# Base.net
KiCad netlist of a schematic drawn in EAGLE
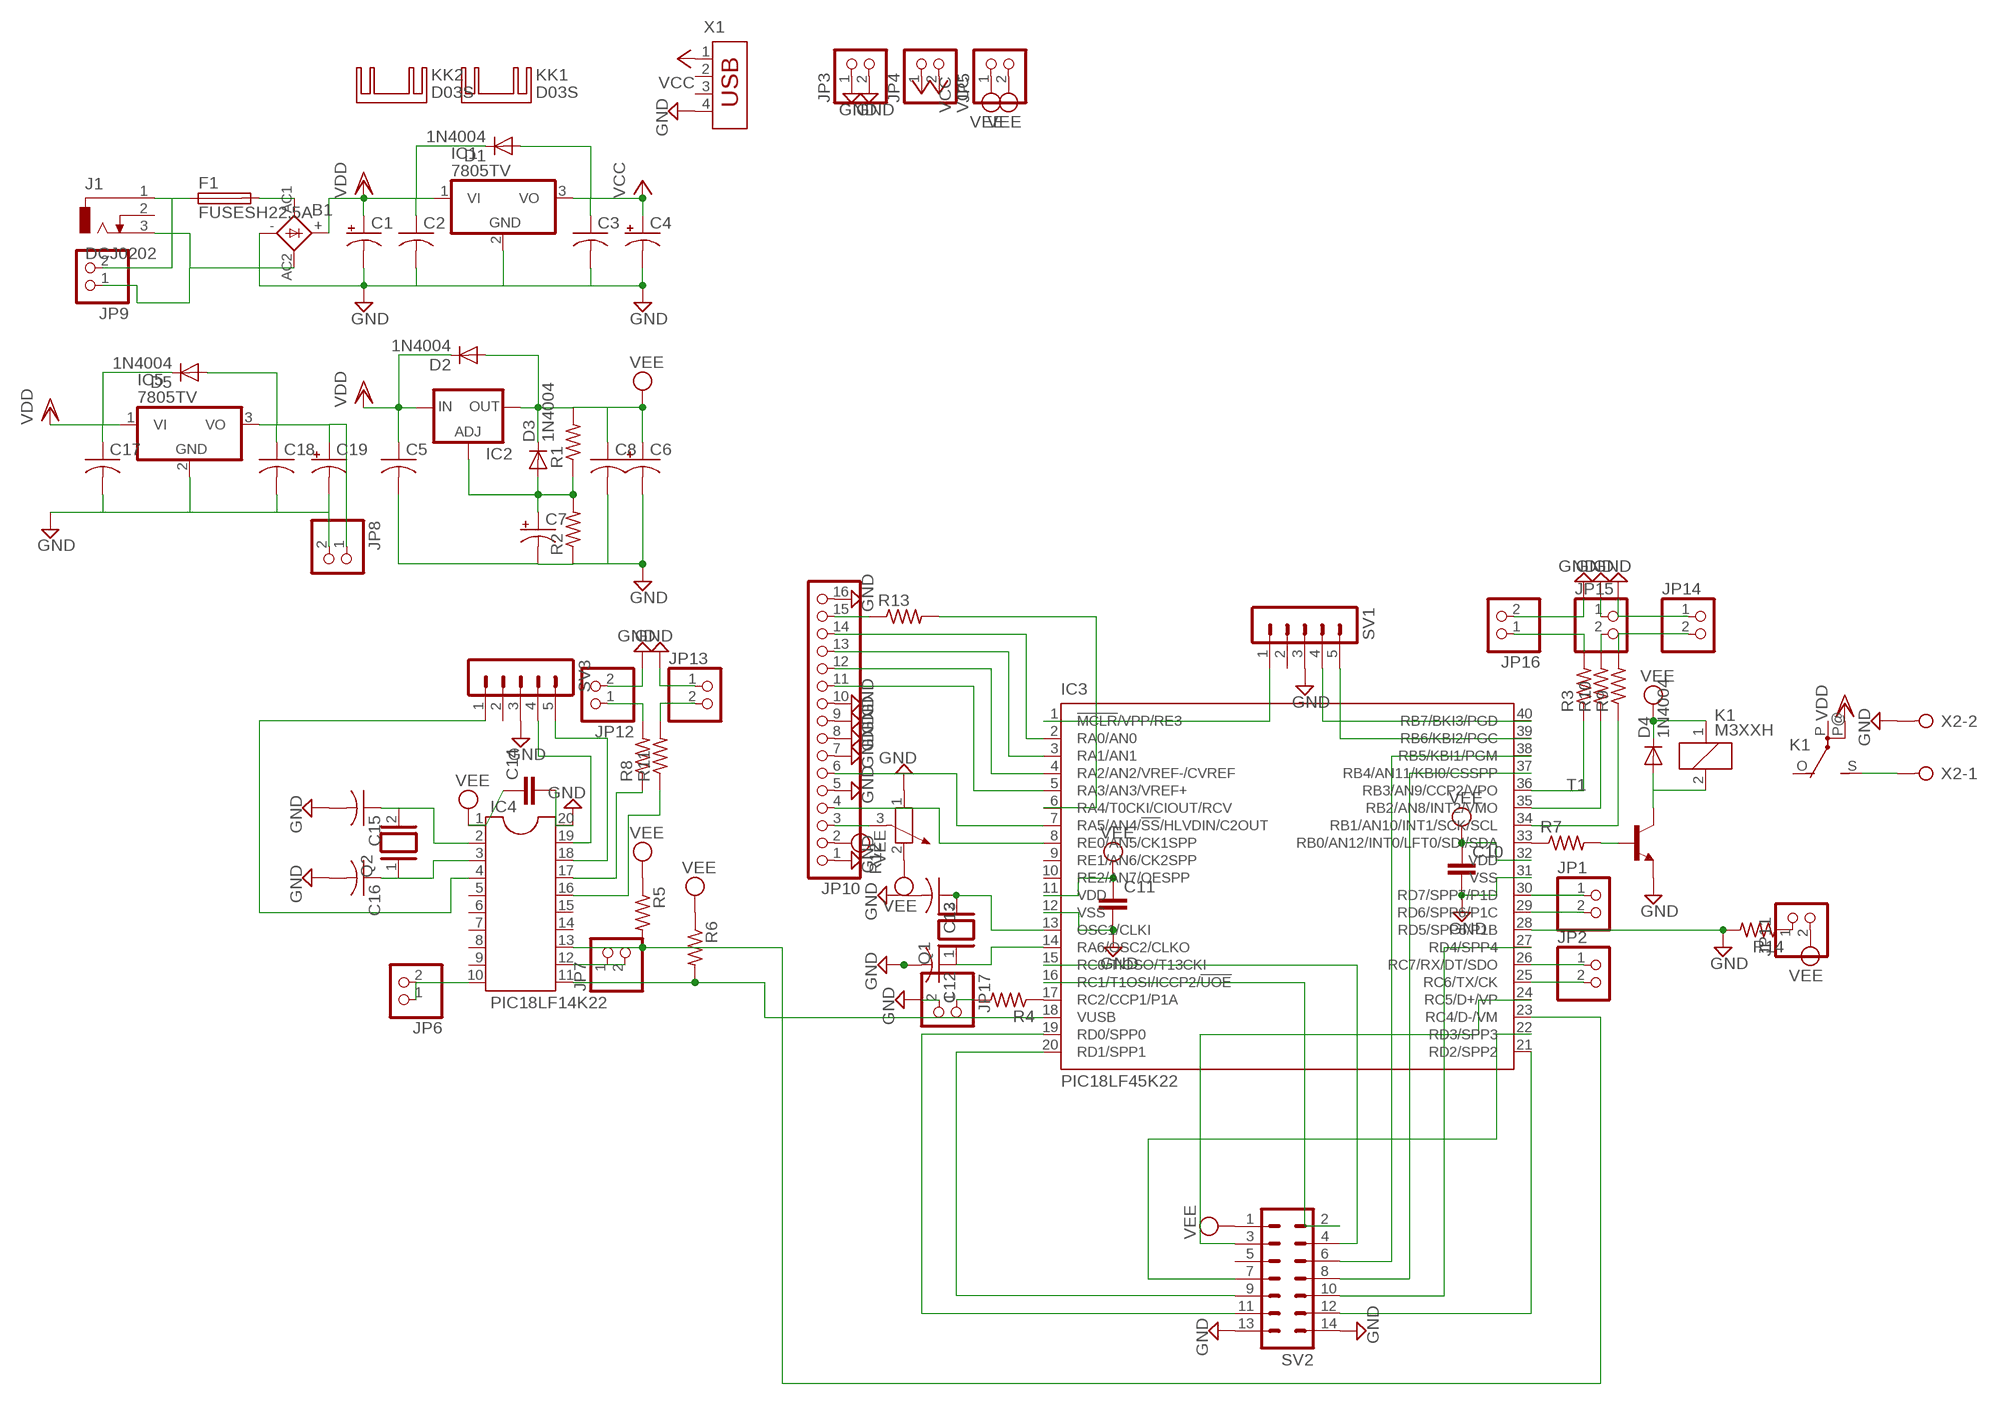
[diagram p0: schematic, sheet 1]

(export (version "E")
  (design (tool "Eeschema 10.0.6"))
  (components
    (comp (ref "B1")
      (value "1KAB")
      (footprint "eagle-import:1KAB")
      (libsource (lib "eagle-import") (part "1KAB"))
    )
    (comp (ref "C1")
      (value "CPOL-USE5-13")
      (footprint "eagle-import:E5-13")
      (libsource (lib "eagle-import") (part "CPOL-USE5-13"))
    )
    (comp (ref "C2")
      (value "C-US050-030X075")
      (footprint "eagle-import:C050-030X075")
      (libsource (lib "eagle-import") (part "C-US050-030X075"))
    )
    (comp (ref "C3")
      (value "C-US050-030X075")
      (footprint "eagle-import:C050-030X075")
      (libsource (lib "eagle-import") (part "C-US050-030X075"))
    )
    (comp (ref "C4")
      (value "CPOL-USE5-13")
      (footprint "eagle-import:E5-13")
      (libsource (lib "eagle-import") (part "CPOL-USE5-13"))
    )
    (comp (ref "C5")
      (value "C-US050-030X075")
      (footprint "eagle-import:C050-030X075")
      (libsource (lib "eagle-import") (part "C-US050-030X075"))
    )
    (comp (ref "C6")
      (value "CPOL-USE2.5-7")
      (footprint "eagle-import:E2,5-7")
      (libsource (lib "eagle-import") (part "CPOL-USE2.5-7"))
    )
    (comp (ref "C7")
      (value "CPOL-USE2.5-5")
      (footprint "eagle-import:E2,5-5")
      (libsource (lib "eagle-import") (part "CPOL-USE2.5-5"))
    )
    (comp (ref "C8")
      (value "C-US050-030X075")
      (footprint "eagle-import:C050-030X075")
      (libsource (lib "eagle-import") (part "C-US050-030X075"))
    )
    (comp (ref "C10")
      (value "C-EU025-030X050")
      (footprint "eagle-import:C025-030X050")
      (libsource (lib "eagle-import") (part "C-EU025-030X050"))
    )
    (comp (ref "C11")
      (value "C-EU025-030X050")
      (footprint "eagle-import:C025-030X050")
      (libsource (lib "eagle-import") (part "C-EU025-030X050"))
    )
    (comp (ref "C12")
      (value "C-US025-030X050")
      (footprint "eagle-import:C025-030X050")
      (libsource (lib "eagle-import") (part "C-US025-030X050"))
    )
    (comp (ref "C13")
      (value "C-US025-030X050")
      (footprint "eagle-import:C025-030X050")
      (libsource (lib "eagle-import") (part "C-US025-030X050"))
    )
    (comp (ref "C14")
      (value "C-EU025-030X050")
      (footprint "eagle-import:C025-030X050")
      (libsource (lib "eagle-import") (part "C-EU025-030X050"))
    )
    (comp (ref "C15")
      (value "C-US025-030X050")
      (footprint "eagle-import:C025-030X050")
      (libsource (lib "eagle-import") (part "C-US025-030X050"))
    )
    (comp (ref "C16")
      (value "C-US025-030X050")
      (footprint "eagle-import:C025-030X050")
      (libsource (lib "eagle-import") (part "C-US025-030X050"))
    )
    (comp (ref "C17")
      (value "C-US050-030X075")
      (footprint "eagle-import:C050-030X075")
      (libsource (lib "eagle-import") (part "C-US050-030X075"))
    )
    (comp (ref "C18")
      (value "C-US050-030X075")
      (footprint "eagle-import:C050-030X075")
      (libsource (lib "eagle-import") (part "C-US050-030X075"))
    )
    (comp (ref "C19")
      (value "CPOL-USE5-10.5")
      (footprint "eagle-import:E5-10,5")
      (libsource (lib "eagle-import") (part "CPOL-USE5-10.5"))
    )
    (comp (ref "D1")
      (value "1N4004")
      (footprint "eagle-import:DO41-10")
      (libsource (lib "eagle-import") (part "1N4004"))
    )
    (comp (ref "D2")
      (value "1N4004")
      (footprint "eagle-import:DO41-10")
      (libsource (lib "eagle-import") (part "1N4004"))
    )
    (comp (ref "D3")
      (value "1N4004")
      (footprint "eagle-import:DO41-10")
      (libsource (lib "eagle-import") (part "1N4004"))
    )
    (comp (ref "D4")
      (value "1N4004")
      (footprint "eagle-import:DO41-10")
      (libsource (lib "eagle-import") (part "1N4004"))
    )
    (comp (ref "D5")
      (value "1N4004")
      (footprint "eagle-import:DO41-10")
      (libsource (lib "eagle-import") (part "1N4004"))
    )
    (comp (ref "F1")
      (value "FUSESH22,5A")
      (footprint "eagle-import:SH22,5A")
      (libsource (lib "eagle-import") (part "FUSESH22,5A"))
    )
    (comp (ref "IC1")
      (value "7805TV")
      (footprint "eagle-import:TO220V")
      (libsource (lib "eagle-import") (part "78TV05"))
    )
    (comp (ref "IC2")
      (value "LM317TS")
      (footprint "eagle-import:317TS")
      (libsource (lib "eagle-import") (part "LM317TS"))
    )
    (comp (ref "IC3")
      (value "PIC18LF45K22")
      (footprint "eagle-import:DIL40")
      (fields (field (name "MF") "MICROCHIP") (field (name "MPN") "PIC18F4550-I/P"))
      (libsource (lib "eagle-import") (part "PIC18F4_40550"))
    )
    (comp (ref "IC4")
      (value "PIC18LF14K22")
      (footprint "eagle-import:DIL20")
      (libsource (lib "eagle-import") (part "DIL20"))
    )
    (comp (ref "IC5")
      (value "7805TV")
      (footprint "eagle-import:TO220V")
      (libsource (lib "eagle-import") (part "78TV05"))
    )
    (comp (ref "J1")
      (value "DCJ0202")
      (footprint "eagle-import:DCJ0202")
      (libsource (lib "eagle-import") (part "DCJ0202"))
    )
    (comp (ref "JP1")
      (value "PINHD-1X2")
      (footprint "eagle-import:1X02")
      (libsource (lib "eagle-import") (part "PINHD-1X2"))
    )
    (comp (ref "JP2")
      (value "PINHD-1X2")
      (footprint "eagle-import:1X02")
      (libsource (lib "eagle-import") (part "PINHD-1X2"))
    )
    (comp (ref "JP3")
      (value "PINHD-1X2")
      (footprint "eagle-import:1X02")
      (libsource (lib "eagle-import") (part "PINHD-1X2"))
    )
    (comp (ref "JP4")
      (value "PINHD-1X2")
      (footprint "eagle-import:1X02")
      (libsource (lib "eagle-import") (part "PINHD-1X2"))
    )
    (comp (ref "JP5")
      (value "PINHD-1X2")
      (footprint "eagle-import:1X02")
      (libsource (lib "eagle-import") (part "PINHD-1X2"))
    )
    (comp (ref "JP6")
      (value "PINHD-1X2")
      (footprint "eagle-import:1X02")
      (libsource (lib "eagle-import") (part "PINHD-1X2"))
    )
    (comp (ref "JP7")
      (value "PINHD-1X2")
      (footprint "eagle-import:1X02")
      (libsource (lib "eagle-import") (part "PINHD-1X2"))
    )
    (comp (ref "JP8")
      (value "PINHD-1X2")
      (footprint "eagle-import:1X02")
      (libsource (lib "eagle-import") (part "PINHD-1X2"))
    )
    (comp (ref "JP9")
      (value "PINHD-1X2")
      (footprint "eagle-import:1X02")
      (libsource (lib "eagle-import") (part "PINHD-1X2"))
    )
    (comp (ref "JP10")
      (value "PINHD-1X16")
      (footprint "eagle-import:1X16")
      (libsource (lib "eagle-import") (part "PINHD-1X16"))
    )
    (comp (ref "JP11")
      (value "PINHD-1X2")
      (footprint "eagle-import:1X02")
      (libsource (lib "eagle-import") (part "PINHD-1X2"))
    )
    (comp (ref "JP12")
      (value "PINHD-1X2")
      (footprint "eagle-import:1X02")
      (libsource (lib "eagle-import") (part "PINHD-1X2"))
    )
    (comp (ref "JP13")
      (value "PINHD-1X2")
      (footprint "eagle-import:1X02")
      (libsource (lib "eagle-import") (part "PINHD-1X2"))
    )
    (comp (ref "JP14")
      (value "PINHD-1X2")
      (footprint "eagle-import:1X02")
      (libsource (lib "eagle-import") (part "PINHD-1X2"))
    )
    (comp (ref "JP15")
      (value "PINHD-1X2")
      (footprint "eagle-import:1X02")
      (libsource (lib "eagle-import") (part "PINHD-1X2"))
    )
    (comp (ref "JP16")
      (value "PINHD-1X2")
      (footprint "eagle-import:1X02")
      (libsource (lib "eagle-import") (part "PINHD-1X2"))
    )
    (comp (ref "JP17")
      (value "PINHD-1X2")
      (footprint "eagle-import:1X02")
      (libsource (lib "eagle-import") (part "PINHD-1X2"))
    )
    (comp (ref "K1")
      (value "M3XXH")
      (footprint "eagle-import:M3XXH")
      (libsource (lib "eagle-import") (part "M3XXH"))
    )
    (comp (ref "KK1")
      (value "D03S")
      (footprint "eagle-import:D03S")
      (libsource (lib "eagle-import") (part "D03S"))
    )
    (comp (ref "KK2")
      (value "D03S")
      (footprint "eagle-import:D03S")
      (libsource (lib "eagle-import") (part "D03S"))
    )
    (comp (ref "Q1")
      (value "XTAL/S")
      (footprint "eagle-import:QS")
      (libsource (lib "eagle-import") (part "XTAL/S"))
    )
    (comp (ref "Q2")
      (value "XTAL/S")
      (footprint "eagle-import:QS")
      (libsource (lib "eagle-import") (part "XTAL/S"))
    )
    (comp (ref "R1")
      (value "R-US_0207/10")
      (footprint "eagle-import:0207_10")
      (libsource (lib "eagle-import") (part "R-US_0207/10"))
    )
    (comp (ref "R2")
      (value "R-US_0207/10")
      (footprint "eagle-import:0207_10")
      (libsource (lib "eagle-import") (part "R-US_0207/10"))
    )
    (comp (ref "R3")
      (value "R-US_0207/10")
      (footprint "eagle-import:0207_10")
      (libsource (lib "eagle-import") (part "R-US_0207/10"))
    )
    (comp (ref "R4")
      (value "R-US_0207/10")
      (footprint "eagle-import:0207_10")
      (libsource (lib "eagle-import") (part "R-US_0207/10"))
    )
    (comp (ref "R5")
      (value "R-US_0207/10")
      (footprint "eagle-import:0207_10")
      (libsource (lib "eagle-import") (part "R-US_0207/10"))
    )
    (comp (ref "R6")
      (value "R-US_0207/10")
      (footprint "eagle-import:0207_10")
      (libsource (lib "eagle-import") (part "R-US_0207/10"))
    )
    (comp (ref "R7")
      (value "R-US_0207/10")
      (footprint "eagle-import:0207_10")
      (libsource (lib "eagle-import") (part "R-US_0207/10"))
    )
    (comp (ref "R8")
      (value "R-US_0207/10")
      (footprint "eagle-import:0207_10")
      (libsource (lib "eagle-import") (part "R-US_0207/10"))
    )
    (comp (ref "R9")
      (value "R-US_0207/10")
      (footprint "eagle-import:0207_10")
      (libsource (lib "eagle-import") (part "R-US_0207/10"))
    )
    (comp (ref "R10")
      (value "R-US_0207/10")
      (footprint "eagle-import:0207_10")
      (libsource (lib "eagle-import") (part "R-US_0207/10"))
    )
    (comp (ref "R11")
      (value "R-US_0207/10")
      (footprint "eagle-import:0207_10")
      (libsource (lib "eagle-import") (part "R-US_0207/10"))
    )
    (comp (ref "R12")
      (value "POTENTIOMETER_PT-10")
      (footprint "eagle-import:PT-10")
      (libsource (lib "eagle-import") (part "POTENTIOMETER_PT-10"))
    )
    (comp (ref "R13")
      (value "R-US_0207/10")
      (footprint "eagle-import:0207_10")
      (libsource (lib "eagle-import") (part "R-US_0207/10"))
    )
    (comp (ref "R14")
      (value "R-US_0207/10")
      (footprint "eagle-import:0207_10")
      (libsource (lib "eagle-import") (part "R-US_0207/10"))
    )
    (comp (ref "SV1")
      (value "MA05-1")
      (footprint "eagle-import:MA05-1")
      (libsource (lib "eagle-import") (part "MA05-1"))
    )
    (comp (ref "SV2")
      (value "MA07-2")
      (footprint "eagle-import:MA07-2")
      (libsource (lib "eagle-import") (part "MA07-2"))
    )
    (comp (ref "SV3")
      (value "MA05-1")
      (footprint "eagle-import:MA05-1")
      (fields (field (name "OC_FARNELL") "unknown") (field (name "OC_NEWARK") "unknown"))
      (libsource (lib "eagle-import") (part "MA05-1"))
    )
    (comp (ref "T1")
      (value "BC547-NPN-TO92-CBE")
      (footprint "eagle-import:TO92-CBE")
      (libsource (lib "eagle-import") (part "-NPN-TO92-CBEBC547"))
    )
    (comp (ref "X1")
      (value "USB-787616")
      (footprint "eagle-import:USB")
      (libsource (lib "eagle-import") (part "USB-787616"))
    )
    (comp (ref "X2")
      (value "W237-02P")
      (footprint "eagle-import:W237-132")
      (libsource (lib "eagle-import") (part "W237-02P"))
    )
  )
  (nets
    (net (code "1") (name "GND") (class "Default")
      (node (ref "B1") (pin "-") (pinfunction "-_-") (pintype "passive"))
      (node (ref "C1") (pin "-") (pinfunction "-_-") (pintype "passive"))
      (node (ref "C10") (pin "2") (pinfunction "2_2") (pintype "passive"))
      (node (ref "C11") (pin "2") (pinfunction "2_2") (pintype "passive"))
      (node (ref "C12") (pin "2") (pinfunction "2_2") (pintype "passive"))
      (node (ref "C13") (pin "2") (pinfunction "2_2") (pintype "passive"))
      (node (ref "C14") (pin "2") (pinfunction "2_2") (pintype "passive"))
      (node (ref "C15") (pin "2") (pinfunction "2_2") (pintype "passive"))
      (node (ref "C16") (pin "2") (pinfunction "2_2") (pintype "passive"))
      (node (ref "C17") (pin "2") (pinfunction "2_2") (pintype "passive"))
      (node (ref "C18") (pin "2") (pinfunction "2_2") (pintype "passive"))
      (node (ref "C19") (pin "-") (pinfunction "-_-") (pintype "passive"))
      (node (ref "C2") (pin "2") (pinfunction "2_2") (pintype "passive"))
      (node (ref "C3") (pin "2") (pinfunction "2_2") (pintype "passive"))
      (node (ref "C4") (pin "-") (pinfunction "-_-") (pintype "passive"))
      (node (ref "C5") (pin "2") (pinfunction "2_2") (pintype "passive"))
      (node (ref "C6") (pin "-") (pinfunction "-_-") (pintype "passive"))
      (node (ref "C7") (pin "-") (pinfunction "-_-") (pintype "passive"))
      (node (ref "C8") (pin "2") (pinfunction "2_2") (pintype "passive"))
      (node (ref "IC1") (pin "2") (pinfunction "GND_2") (pintype "passive"))
      (node (ref "IC3") (pin "12") (pinfunction "VSS_12") (pintype "power_in"))
      (node (ref "IC3") (pin "28") (pinfunction "RD5/SPP5/P1B_28") (pintype "bidirectional"))
      (node (ref "IC3") (pin "31") (pinfunction "VSS_31") (pintype "power_in"))
      (node (ref "IC4") (pin "20") (pinfunction "20_20") (pintype "passive"))
      (node (ref "IC5") (pin "2") (pinfunction "GND_2") (pintype "passive"))
      (node (ref "JP10") (pin "1") (pinfunction "1_1") (pintype "passive"))
      (node (ref "JP10") (pin "10") (pinfunction "10_10") (pintype "passive"))
      (node (ref "JP10") (pin "16") (pinfunction "16_16") (pintype "passive"))
      (node (ref "JP10") (pin "5") (pinfunction "5_5") (pintype "passive"))
      (node (ref "JP10") (pin "7") (pinfunction "7_7") (pintype "passive"))
      (node (ref "JP10") (pin "8") (pinfunction "8_8") (pintype "passive"))
      (node (ref "JP10") (pin "9") (pinfunction "9_9") (pintype "passive"))
      (node (ref "JP12") (pin "2") (pinfunction "2_2") (pintype "passive"))
      (node (ref "JP13") (pin "1") (pinfunction "1_1") (pintype "passive"))
      (node (ref "JP14") (pin "1") (pinfunction "1_1") (pintype "passive"))
      (node (ref "JP15") (pin "1") (pinfunction "1_1") (pintype "passive"))
      (node (ref "JP16") (pin "2") (pinfunction "2_2") (pintype "passive"))
      (node (ref "JP17") (pin "2") (pinfunction "2_2") (pintype "passive"))
      (node (ref "JP3") (pin "1") (pinfunction "1_1") (pintype "passive"))
      (node (ref "JP3") (pin "2") (pinfunction "2_2") (pintype "passive"))
      (node (ref "JP8") (pin "2") (pinfunction "2_2") (pintype "passive"))
      (node (ref "R12") (pin "1") (pinfunction "1_1") (pintype "passive"))
      (node (ref "R14") (pin "2") (pinfunction "2_2") (pintype "passive"))
      (node (ref "R2") (pin "1") (pinfunction "1_1") (pintype "passive"))
      (node (ref "SV1") (pin "3") (pinfunction "3_3") (pintype "passive"))
      (node (ref "SV2") (pin "13") (pinfunction "13_13") (pintype "passive"))
      (node (ref "SV2") (pin "14") (pinfunction "14_14") (pintype "passive"))
      (node (ref "SV3") (pin "3") (pinfunction "3_3") (pintype "passive"))
      (node (ref "T1") (pin "E") (pinfunction "E_E") (pintype "passive"))
      (node (ref "X1") (pin "4") (pinfunction "4_4") (pintype "passive"))
      (node (ref "X2") (pin "2") (pinfunction "KL_2") (pintype "passive"))
    )
    (net (code "2") (name "Net-(B1-PadAC1)") (class "Default")
      (node (ref "B1") (pin "AC1") (pinfunction "AC1_AC1") (pintype "passive"))
      (node (ref "F1") (pin "2") (pinfunction "2_2") (pintype "passive"))
    )
    (net (code "3") (name "Net-(B1-PadAC2)") (class "Default")
      (node (ref "B1") (pin "AC2") (pinfunction "AC2_AC2") (pintype "passive"))
      (node (ref "J1") (pin "3") (pinfunction "3_3") (pintype "passive"))
      (node (ref "JP9") (pin "1") (pinfunction "1_1") (pintype "passive"))
    )
    (net (code "4") (name "Net-(C15-Pad1)") (class "Default")
      (node (ref "C15") (pin "1") (pinfunction "1_1") (pintype "passive"))
      (node (ref "IC4") (pin "2") (pinfunction "2_2") (pintype "passive"))
      (node (ref "Q2") (pin "2") (pinfunction "2_2") (pintype "passive"))
    )
    (net (code "5") (name "Net-(C16-Pad1)") (class "Default")
      (node (ref "C16") (pin "1") (pinfunction "1_1") (pintype "passive"))
      (node (ref "IC4") (pin "3") (pinfunction "3_3") (pintype "passive"))
      (node (ref "Q2") (pin "1") (pinfunction "1_1") (pintype "passive"))
    )
    (net (code "6") (name "Net-(D4-PadA)") (class "Default")
      (node (ref "D4") (pin "A") (pinfunction "A_A") (pintype "passive"))
      (node (ref "K1") (pin "2") (pinfunction "2_2") (pintype "passive"))
      (node (ref "T1") (pin "C") (pinfunction "C_C") (pintype "passive"))
    )
    (net (code "7") (name "Net-(F1-Pad1)") (class "Default")
      (node (ref "F1") (pin "1") (pinfunction "1_1") (pintype "passive"))
      (node (ref "J1") (pin "1") (pinfunction "1_1") (pintype "passive"))
      (node (ref "JP9") (pin "2") (pinfunction "2_2") (pintype "passive"))
    )
    (net (code "8") (name "Net-(IC2-ADJ)") (class "Default")
      (node (ref "C7") (pin "+") (pinfunction "+_+") (pintype "passive"))
      (node (ref "D3") (pin "A") (pinfunction "A_A") (pintype "passive"))
      (node (ref "IC2") (pin "1") (pinfunction "ADJ_1") (pintype "input"))
      (node (ref "R1") (pin "1") (pinfunction "1_1") (pintype "passive"))
      (node (ref "R2") (pin "2") (pinfunction "2_2") (pintype "passive"))
    )
    (net (code "9") (name "Net-(IC3-OSC1{slash}CLKI)") (class "Default")
      (node (ref "C13") (pin "1") (pinfunction "1_1") (pintype "passive"))
      (node (ref "IC3") (pin "13") (pinfunction "OSC1/CLKI_13") (pintype "input"))
      (node (ref "Q1") (pin "2") (pinfunction "2_2") (pintype "passive"))
    )
    (net (code "10") (name "Net-(IC3-RA0{slash}AN0)") (class "Default")
      (node (ref "IC3") (pin "2") (pinfunction "RA0/AN0_2") (pintype "bidirectional"))
      (node (ref "JP10") (pin "14") (pinfunction "14_14") (pintype "passive"))
    )
    (net (code "11") (name "Net-(IC3-RA1{slash}AN1)") (class "Default")
      (node (ref "IC3") (pin "3") (pinfunction "RA1/AN1_3") (pintype "bidirectional"))
      (node (ref "JP10") (pin "13") (pinfunction "13_13") (pintype "passive"))
    )
    (net (code "12") (name "Net-(IC3-RA2{slash}AN2{slash}VREF-{slash}CVREF)") (class "Default")
      (node (ref "IC3") (pin "4") (pinfunction "RA2/AN2/VREF-/CVREF_4") (pintype "bidirectional"))
      (node (ref "JP10") (pin "12") (pinfunction "12_12") (pintype "passive"))
    )
    (net (code "13") (name "Net-(IC3-RA3{slash}AN3{slash}VREF+)") (class "Default")
      (node (ref "IC3") (pin "5") (pinfunction "RA3/AN3/VREF+_5") (pintype "bidirectional"))
      (node (ref "JP10") (pin "11") (pinfunction "11_11") (pintype "passive"))
    )
    (net (code "14") (name "Net-(IC3-RA4{slash}T0CKI{slash}CIOUT{slash}RCV)") (class "Default")
      (node (ref "IC3") (pin "6") (pinfunction "RA4/T0CKI/CIOUT/RCV_6") (pintype "bidirectional"))
      (node (ref "R13") (pin "2") (pinfunction "2_2") (pintype "passive"))
    )
    (net (code "15") (name "Net-(IC3-RA5{slash}AN4{slash}~{SS}{slash}HLVDIN{slash}C2OUT)") (class "Default")
      (node (ref "IC3") (pin "7") (pinfunction "RA5/AN4/~{SS}/HLVDIN/C2OUT_7") (pintype "bidirectional"))
      (node (ref "JP10") (pin "6") (pinfunction "6_6") (pintype "passive"))
    )
    (net (code "16") (name "Net-(IC3-RA6{slash}OSC2{slash}CLKO)") (class "Default")
      (node (ref "C12") (pin "1") (pinfunction "1_1") (pintype "passive"))
      (node (ref "IC3") (pin "14") (pinfunction "RA6/OSC2/CLKO_14") (pintype "output"))
      (node (ref "Q1") (pin "1") (pinfunction "1_1") (pintype "passive"))
    )
    (net (code "17") (name "Net-(IC3-RB0{slash}AN12{slash}INT0{slash}LFT0{slash}SDI{slash}SDA)") (class "Default")
      (node (ref "IC3") (pin "33") (pinfunction "RB0/AN12/INT0/LFT0/SDI/SDA_33") (pintype "bidirectional"))
      (node (ref "R7") (pin "1") (pinfunction "1_1") (pintype "passive"))
    )
    (net (code "18") (name "Net-(IC3-RB1{slash}AN10{slash}INT1{slash}SCK{slash}SCL)") (class "Default")
      (node (ref "IC3") (pin "34") (pinfunction "RB1/AN10/INT1/SCK/SCL_34") (pintype "bidirectional"))
      (node (ref "R9") (pin "1") (pinfunction "1_1") (pintype "passive"))
    )
    (net (code "19") (name "Net-(IC3-RB2{slash}AN8{slash}INT2{slash}VMO)") (class "Default")
      (node (ref "IC3") (pin "35") (pinfunction "RB2/AN8/INT2/VMO_35") (pintype "bidirectional"))
      (node (ref "R10") (pin "1") (pinfunction "1_1") (pintype "passive"))
    )
    (net (code "20") (name "Net-(IC3-RB3{slash}AN9{slash}CCP2{slash}VPO)") (class "Default")
      (node (ref "IC3") (pin "36") (pinfunction "RB3/AN9/CCP2/VPO_36") (pintype "bidirectional"))
      (node (ref "R3") (pin "1") (pinfunction "1_1") (pintype "passive"))
    )
    (net (code "21") (name "Net-(IC3-RB4{slash}AN11{slash}KBI0{slash}CSSPP)") (class "Default")
      (node (ref "IC3") (pin "37") (pinfunction "RB4/AN11/KBI0/CSSPP_37") (pintype "bidirectional"))
      (node (ref "SV2") (pin "8") (pinfunction "8_8") (pintype "passive"))
    )
    (net (code "22") (name "Net-(IC3-RB5{slash}KBI1{slash}PGM)") (class "Default")
      (node (ref "IC3") (pin "38") (pinfunction "RB5/KBI1/PGM_38") (pintype "bidirectional"))
      (node (ref "SV2") (pin "6") (pinfunction "6_6") (pintype "passive"))
    )
    (net (code "23") (name "Net-(IC3-RB6{slash}KBI2{slash}PGC)") (class "Default")
      (node (ref "IC3") (pin "39") (pinfunction "RB6/KBI2/PGC_39") (pintype "bidirectional"))
      (node (ref "SV1") (pin "5") (pinfunction "5_5") (pintype "passive"))
    )
    (net (code "24") (name "Net-(IC3-RB7{slash}BKI3{slash}PGD)") (class "Default")
      (node (ref "IC3") (pin "40") (pinfunction "RB7/BKI3/PGD_40") (pintype "bidirectional"))
      (node (ref "SV1") (pin "4") (pinfunction "4_4") (pintype "passive"))
    )
    (net (code "25") (name "Net-(IC3-RC0{slash}TIOSO{slash}T13CKI)") (class "Default")
      (node (ref "IC3") (pin "15") (pinfunction "RC0/TIOSO/T13CKI_15") (pintype "bidirectional"))
      (node (ref "SV2") (pin "4") (pinfunction "4_4") (pintype "passive"))
    )
    (net (code "26") (name "Net-(IC3-RC1{slash}T1OSI{slash}ICCP2{slash}~{UOE})") (class "Default")
      (node (ref "IC3") (pin "16") (pinfunction "RC1/T1OSI/ICCP2/~{UOE}_16") (pintype "bidirectional"))
      (node (ref "SV2") (pin "2") (pinfunction "2_2") (pintype "passive"))
    )
    (net (code "27") (name "Net-(IC3-RC2{slash}CCP1{slash}P1A)") (class "Default")
      (node (ref "IC3") (pin "17") (pinfunction "RC2/CCP1/P1A_17") (pintype "bidirectional"))
      (node (ref "R4") (pin "1") (pinfunction "1_1") (pintype "passive"))
    )
    (net (code "28") (name "Net-(IC3-RC4{slash}D-{slash}VM)") (class "Default")
      (node (ref "IC3") (pin "23") (pinfunction "RC4/D-/VM_23") (pintype "bidirectional"))
      (node (ref "IC4") (pin "13") (pinfunction "13_13") (pintype "passive"))
      (node (ref "R5") (pin "2") (pinfunction "2_2") (pintype "passive"))
    )
    (net (code "29") (name "Net-(IC3-RC5{slash}D+{slash}VP)") (class "Default")
      (node (ref "IC3") (pin "24") (pinfunction "RC5/D+/VP_24") (pintype "bidirectional"))
      (node (ref "SV2") (pin "3") (pinfunction "3_3") (pintype "passive"))
    )
    (net (code "30") (name "Net-(IC3-RC6{slash}TX{slash}CK)") (class "Default")
      (node (ref "IC3") (pin "25") (pinfunction "RC6/TX/CK_25") (pintype "bidirectional"))
      (node (ref "JP2") (pin "2") (pinfunction "2_2") (pintype "passive"))
    )
    (net (code "31") (name "Net-(IC3-RC7{slash}RX{slash}DT{slash}SDO)") (class "Default")
      (node (ref "IC3") (pin "26") (pinfunction "RC7/RX/DT/SDO_26") (pintype "bidirectional"))
      (node (ref "JP2") (pin "1") (pinfunction "1_1") (pintype "passive"))
    )
    (net (code "32") (name "Net-(IC3-RD0{slash}SPP0)") (class "Default")
      (node (ref "IC3") (pin "19") (pinfunction "RD0/SPP0_19") (pintype "bidirectional"))
      (node (ref "SV2") (pin "11") (pinfunction "11_11") (pintype "passive"))
    )
    (net (code "33") (name "Net-(IC3-RD1{slash}SPP1)") (class "Default")
      (node (ref "IC3") (pin "20") (pinfunction "RD1/SPP1_20") (pintype "bidirectional"))
      (node (ref "SV2") (pin "9") (pinfunction "9_9") (pintype "passive"))
    )
    (net (code "34") (name "Net-(IC3-RD2{slash}SPP2)") (class "Default")
      (node (ref "IC3") (pin "21") (pinfunction "RD2/SPP2_21") (pintype "bidirectional"))
      (node (ref "SV2") (pin "12") (pinfunction "12_12") (pintype "passive"))
    )
    (net (code "35") (name "Net-(IC3-RD3{slash}SPP3)") (class "Default")
      (node (ref "IC3") (pin "22") (pinfunction "RD3/SPP3_22") (pintype "bidirectional"))
      (node (ref "SV2") (pin "7") (pinfunction "7_7") (pintype "passive"))
    )
    (net (code "36") (name "Net-(IC3-RD4{slash}SPP4)") (class "Default")
      (node (ref "IC3") (pin "27") (pinfunction "RD4/SPP4_27") (pintype "bidirectional"))
      (node (ref "SV2") (pin "10") (pinfunction "10_10") (pintype "passive"))
    )
    (net (code "37") (name "Net-(IC3-RD6{slash}SPP6{slash}P1C)") (class "Default")
      (node (ref "IC3") (pin "29") (pinfunction "RD6/SPP6/P1C_29") (pintype "bidirectional"))
      (node (ref "JP1") (pin "2") (pinfunction "2_2") (pintype "passive"))
    )
    (net (code "38") (name "Net-(IC3-RD7{slash}SPP7{slash}P1D)") (class "Default")
      (node (ref "IC3") (pin "30") (pinfunction "RD7/SPP7/P1D_30") (pintype "bidirectional"))
      (node (ref "JP1") (pin "1") (pinfunction "1_1") (pintype "passive"))
    )
    (net (code "39") (name "Net-(IC3-RE0{slash}AN5{slash}CK1SPP)") (class "Default")
      (node (ref "IC3") (pin "8") (pinfunction "RE0/AN5/CK1SPP_8") (pintype "bidirectional"))
      (node (ref "JP10") (pin "4") (pinfunction "4_4") (pintype "passive"))
    )
    (net (code "40") (name "Net-(IC3-VUSB)") (class "Default")
      (node (ref "IC3") (pin "18") (pinfunction "VUSB_18") (pintype "bidirectional"))
      (node (ref "IC4") (pin "11") (pinfunction "11_11") (pintype "passive"))
      (node (ref "R6") (pin "2") (pinfunction "2_2") (pintype "passive"))
    )
    (net (code "41") (name "Net-(IC3-~{MCLR}{slash}VPP{slash}RE3)") (class "Default")
      (node (ref "IC3") (pin "1") (pinfunction "~{MCLR}/VPP/RE3_1") (pintype "input"))
      (node (ref "SV1") (pin "1") (pinfunction "1_1") (pintype "passive"))
    )
    (net (code "42") (name "Net-(IC4-Pad4)") (class "Default")
      (node (ref "IC4") (pin "4") (pinfunction "4_4") (pintype "passive"))
      (node (ref "SV3") (pin "1") (pinfunction "1_1") (pintype "passive"))
    )
    (net (code "43") (name "Net-(IC4-Pad10)") (class "Default")
      (node (ref "IC4") (pin "10") (pinfunction "10_10") (pintype "passive"))
      (node (ref "JP6") (pin "1") (pinfunction "1_1") (pintype "passive"))
      (node (ref "JP6") (pin "2") (pinfunction "2_2") (pintype "passive"))
    )
    (net (code "44") (name "Net-(IC4-Pad12)") (class "Default")
      (node (ref "IC4") (pin "12") (pinfunction "12_12") (pintype "passive"))
      (node (ref "JP7") (pin "1") (pinfunction "1_1") (pintype "passive"))
      (node (ref "JP7") (pin "2") (pinfunction "2_2") (pintype "passive"))
    )
    (net (code "45") (name "Net-(IC4-Pad16)") (class "Default")
      (node (ref "IC4") (pin "16") (pinfunction "16_16") (pintype "passive"))
      (node (ref "R11") (pin "1") (pinfunction "1_1") (pintype "passive"))
    )
    (net (code "46") (name "Net-(IC4-Pad17)") (class "Default")
      (node (ref "IC4") (pin "17") (pinfunction "17_17") (pintype "passive"))
      (node (ref "R8") (pin "1") (pinfunction "1_1") (pintype "passive"))
    )
    (net (code "47") (name "Net-(IC4-Pad18)") (class "Default")
      (node (ref "IC4") (pin "18") (pinfunction "18_18") (pintype "passive"))
      (node (ref "SV3") (pin "5") (pinfunction "5_5") (pintype "passive"))
    )
    (net (code "48") (name "Net-(IC4-Pad19)") (class "Default")
      (node (ref "IC4") (pin "19") (pinfunction "19_19") (pintype "passive"))
      (node (ref "SV3") (pin "4") (pinfunction "4_4") (pintype "passive"))
    )
    (net (code "49") (name "Net-(IC5-VO)") (class "Default")
      (node (ref "C18") (pin "1") (pinfunction "1_1") (pintype "passive"))
      (node (ref "C19") (pin "+") (pinfunction "+_+") (pintype "passive"))
      (node (ref "D5") (pin "A") (pinfunction "A_A") (pintype "passive"))
      (node (ref "IC5") (pin "3") (pinfunction "VO_3") (pintype "passive"))
      (node (ref "JP8") (pin "1") (pinfunction "1_1") (pintype "passive"))
    )
    (net (code "50") (name "Net-(JP10-Pad3)") (class "Default")
      (node (ref "JP10") (pin "3") (pinfunction "3_3") (pintype "passive"))
      (node (ref "R12") (pin "3") (pinfunction "3_3") (pintype "passive"))
    )
    (net (code "51") (name "Net-(JP10-Pad15)") (class "Default")
      (node (ref "JP10") (pin "15") (pinfunction "15_15") (pintype "passive"))
      (node (ref "R13") (pin "1") (pinfunction "1_1") (pintype "passive"))
    )
    (net (code "52") (name "Net-(JP11-Pad1)") (class "Default")
      (node (ref "JP11") (pin "1") (pinfunction "1_1") (pintype "passive"))
      (node (ref "R14") (pin "1") (pinfunction "1_1") (pintype "passive"))
    )
    (net (code "53") (name "Net-(JP12-Pad1)") (class "Default")
      (node (ref "JP12") (pin "1") (pinfunction "1_1") (pintype "passive"))
      (node (ref "R8") (pin "2") (pinfunction "2_2") (pintype "passive"))
    )
    (net (code "54") (name "Net-(JP13-Pad2)") (class "Default")
      (node (ref "JP13") (pin "2") (pinfunction "2_2") (pintype "passive"))
      (node (ref "R11") (pin "2") (pinfunction "2_2") (pintype "passive"))
    )
    (net (code "55") (name "Net-(JP14-Pad2)") (class "Default")
      (node (ref "JP14") (pin "2") (pinfunction "2_2") (pintype "passive"))
      (node (ref "R9") (pin "2") (pinfunction "2_2") (pintype "passive"))
    )
    (net (code "56") (name "Net-(JP15-Pad2)") (class "Default")
      (node (ref "JP15") (pin "2") (pinfunction "2_2") (pintype "passive"))
      (node (ref "R10") (pin "2") (pinfunction "2_2") (pintype "passive"))
    )
    (net (code "57") (name "Net-(JP16-Pad1)") (class "Default")
      (node (ref "JP16") (pin "1") (pinfunction "1_1") (pintype "passive"))
      (node (ref "R3") (pin "2") (pinfunction "2_2") (pintype "passive"))
    )
    (net (code "58") (name "Net-(JP17-Pad1)") (class "Default")
      (node (ref "JP17") (pin "1") (pinfunction "1_1") (pintype "passive"))
      (node (ref "R4") (pin "2") (pinfunction "2_2") (pintype "passive"))
    )
    (net (code "59") (name "Net-(R7-Pad2)") (class "Default")
      (node (ref "R7") (pin "2") (pinfunction "2_2") (pintype "passive"))
      (node (ref "T1") (pin "B") (pinfunction "B_B") (pintype "passive"))
    )
    (net (code "60") (name "Net-(X2A-KL)") (class "Default")
      (node (ref "K1") (pin "S") (pinfunction "S_S") (pintype "passive"))
      (node (ref "X2") (pin "1") (pinfunction "KL_1") (pintype "passive"))
    )
    (net (code "61") (name "VCC") (class "Default")
      (node (ref "C3") (pin "1") (pinfunction "1_1") (pintype "passive"))
      (node (ref "C4") (pin "+") (pinfunction "+_+") (pintype "passive"))
      (node (ref "D1") (pin "A") (pinfunction "A_A") (pintype "passive"))
      (node (ref "IC1") (pin "3") (pinfunction "VO_3") (pintype "passive"))
      (node (ref "JP4") (pin "1") (pinfunction "1_1") (pintype "passive"))
      (node (ref "JP4") (pin "2") (pinfunction "2_2") (pintype "passive"))
      (node (ref "X1") (pin "1") (pinfunction "1_1") (pintype "passive"))
    )
    (net (code "62") (name "VDD") (class "Default")
      (node (ref "B1") (pin "+") (pinfunction "+_+") (pintype "passive"))
      (node (ref "C1") (pin "+") (pinfunction "+_+") (pintype "passive"))
      (node (ref "C17") (pin "1") (pinfunction "1_1") (pintype "passive"))
      (node (ref "C2") (pin "1") (pinfunction "1_1") (pintype "passive"))
      (node (ref "C5") (pin "1") (pinfunction "1_1") (pintype "passive"))
      (node (ref "D1") (pin "C") (pinfunction "C_C") (pintype "passive"))
      (node (ref "D2") (pin "C") (pinfunction "C_C") (pintype "passive"))
      (node (ref "D5") (pin "C") (pinfunction "C_C") (pintype "passive"))
      (node (ref "IC1") (pin "1") (pinfunction "VI_1") (pintype "input"))
      (node (ref "IC2") (pin "3") (pinfunction "IN_3") (pintype "input"))
      (node (ref "IC5") (pin "1") (pinfunction "VI_1") (pintype "input"))
      (node (ref "K1") (pin "P@") (pinfunction "P_P@") (pintype "passive"))
    )
    (net (code "63") (name "VEE") (class "Default")
      (node (ref "C10") (pin "1") (pinfunction "1_1") (pintype "passive"))
      (node (ref "C11") (pin "1") (pinfunction "1_1") (pintype "passive"))
      (node (ref "C14") (pin "1") (pinfunction "1_1") (pintype "passive"))
      (node (ref "C6") (pin "+") (pinfunction "+_+") (pintype "passive"))
      (node (ref "C8") (pin "1") (pinfunction "1_1") (pintype "passive"))
      (node (ref "D2") (pin "A") (pinfunction "A_A") (pintype "passive"))
      (node (ref "D3") (pin "C") (pinfunction "C_C") (pintype "passive"))
      (node (ref "D4") (pin "C") (pinfunction "C_C") (pintype "passive"))
      (node (ref "IC2") (pin "2") (pinfunction "OUT_2") (pintype "passive"))
      (node (ref "IC3") (pin "11") (pinfunction "VDD_11") (pintype "power_in"))
      (node (ref "IC3") (pin "32") (pinfunction "VDD_32") (pintype "power_in"))
      (node (ref "IC4") (pin "1") (pinfunction "1_1") (pintype "passive"))
      (node (ref "JP10") (pin "2") (pinfunction "2_2") (pintype "passive"))
      (node (ref "JP11") (pin "2") (pinfunction "2_2") (pintype "passive"))
      (node (ref "JP5") (pin "1") (pinfunction "1_1") (pintype "passive"))
      (node (ref "JP5") (pin "2") (pinfunction "2_2") (pintype "passive"))
      (node (ref "K1") (pin "1") (pinfunction "1_1") (pintype "passive"))
      (node (ref "R1") (pin "2") (pinfunction "2_2") (pintype "passive"))
      (node (ref "R12") (pin "2") (pinfunction "2_2") (pintype "passive"))
      (node (ref "R5") (pin "1") (pinfunction "1_1") (pintype "passive"))
      (node (ref "R6") (pin "1") (pinfunction "1_1") (pintype "passive"))
      (node (ref "SV2") (pin "1") (pinfunction "1_1") (pintype "passive"))
    )
    (net (code "64") (name "unconnected-(IC3-RE1{slash}AN6{slash}CK2SPP-Pad9)") (class "Default")
      (node (ref "IC3") (pin "9") (pinfunction "RE1/AN6/CK2SPP_9") (pintype "bidirectional"))
    )
    (net (code "65") (name "unconnected-(IC3-RE2{slash}AN7{slash}OESPP-Pad10)") (class "Default")
      (node (ref "IC3") (pin "10") (pinfunction "RE2/AN7/OESPP_10") (pintype "bidirectional"))
    )
    (net (code "66") (name "unconnected-(IC4-Pad5)") (class "Default")
      (node (ref "IC4") (pin "5") (pinfunction "5_5") (pintype "passive"))
    )
    (net (code "67") (name "unconnected-(IC4-Pad6)") (class "Default")
      (node (ref "IC4") (pin "6") (pinfunction "6_6") (pintype "passive"))
    )
    (net (code "68") (name "unconnected-(IC4-Pad7)") (class "Default")
      (node (ref "IC4") (pin "7") (pinfunction "7_7") (pintype "passive"))
    )
    (net (code "69") (name "unconnected-(IC4-Pad8)") (class "Default")
      (node (ref "IC4") (pin "8") (pinfunction "8_8") (pintype "passive"))
    )
    (net (code "70") (name "unconnected-(IC4-Pad9)") (class "Default")
      (node (ref "IC4") (pin "9") (pinfunction "9_9") (pintype "passive"))
    )
    (net (code "71") (name "unconnected-(IC4-Pad14)") (class "Default")
      (node (ref "IC4") (pin "14") (pinfunction "14_14") (pintype "passive"))
    )
    (net (code "72") (name "unconnected-(IC4-Pad15)") (class "Default")
      (node (ref "IC4") (pin "15") (pinfunction "15_15") (pintype "passive"))
    )
    (net (code "73") (name "unconnected-(J1-Pad2)") (class "Default")
      (node (ref "J1") (pin "2") (pinfunction "2_2") (pintype "passive"))
    )
    (net (code "74") (name "unconnected-(K1-PadO)") (class "Default")
      (node (ref "K1") (pin "O") (pinfunction "O_O") (pintype "passive"))
    )
    (net (code "75") (name "unconnected-(K1-PadP)") (class "Default")
      (node (ref "K1") (pin "P") (pinfunction "P_P") (pintype "passive"))
    )
    (net (code "76") (name "unconnected-(SV1-Pad2)") (class "Default")
      (node (ref "SV1") (pin "2") (pinfunction "2_2") (pintype "passive"))
    )
    (net (code "77") (name "unconnected-(SV2-Pad5)") (class "Default")
      (node (ref "SV2") (pin "5") (pinfunction "5_5") (pintype "passive"))
    )
    (net (code "78") (name "unconnected-(SV3-Pad2)") (class "Default")
      (node (ref "SV3") (pin "2") (pinfunction "2_2") (pintype "passive"))
    )
    (net (code "79") (name "unconnected-(X1-Pad2)") (class "Default")
      (node (ref "X1") (pin "2") (pinfunction "2_2") (pintype "passive"))
    )
    (net (code "80") (name "unconnected-(X1-Pad3)") (class "Default")
      (node (ref "X1") (pin "3") (pinfunction "3_3") (pintype "passive"))
    )
  )
)
